# brick_lcd.net
KiCad netlist of a schematic drawn in EAGLE
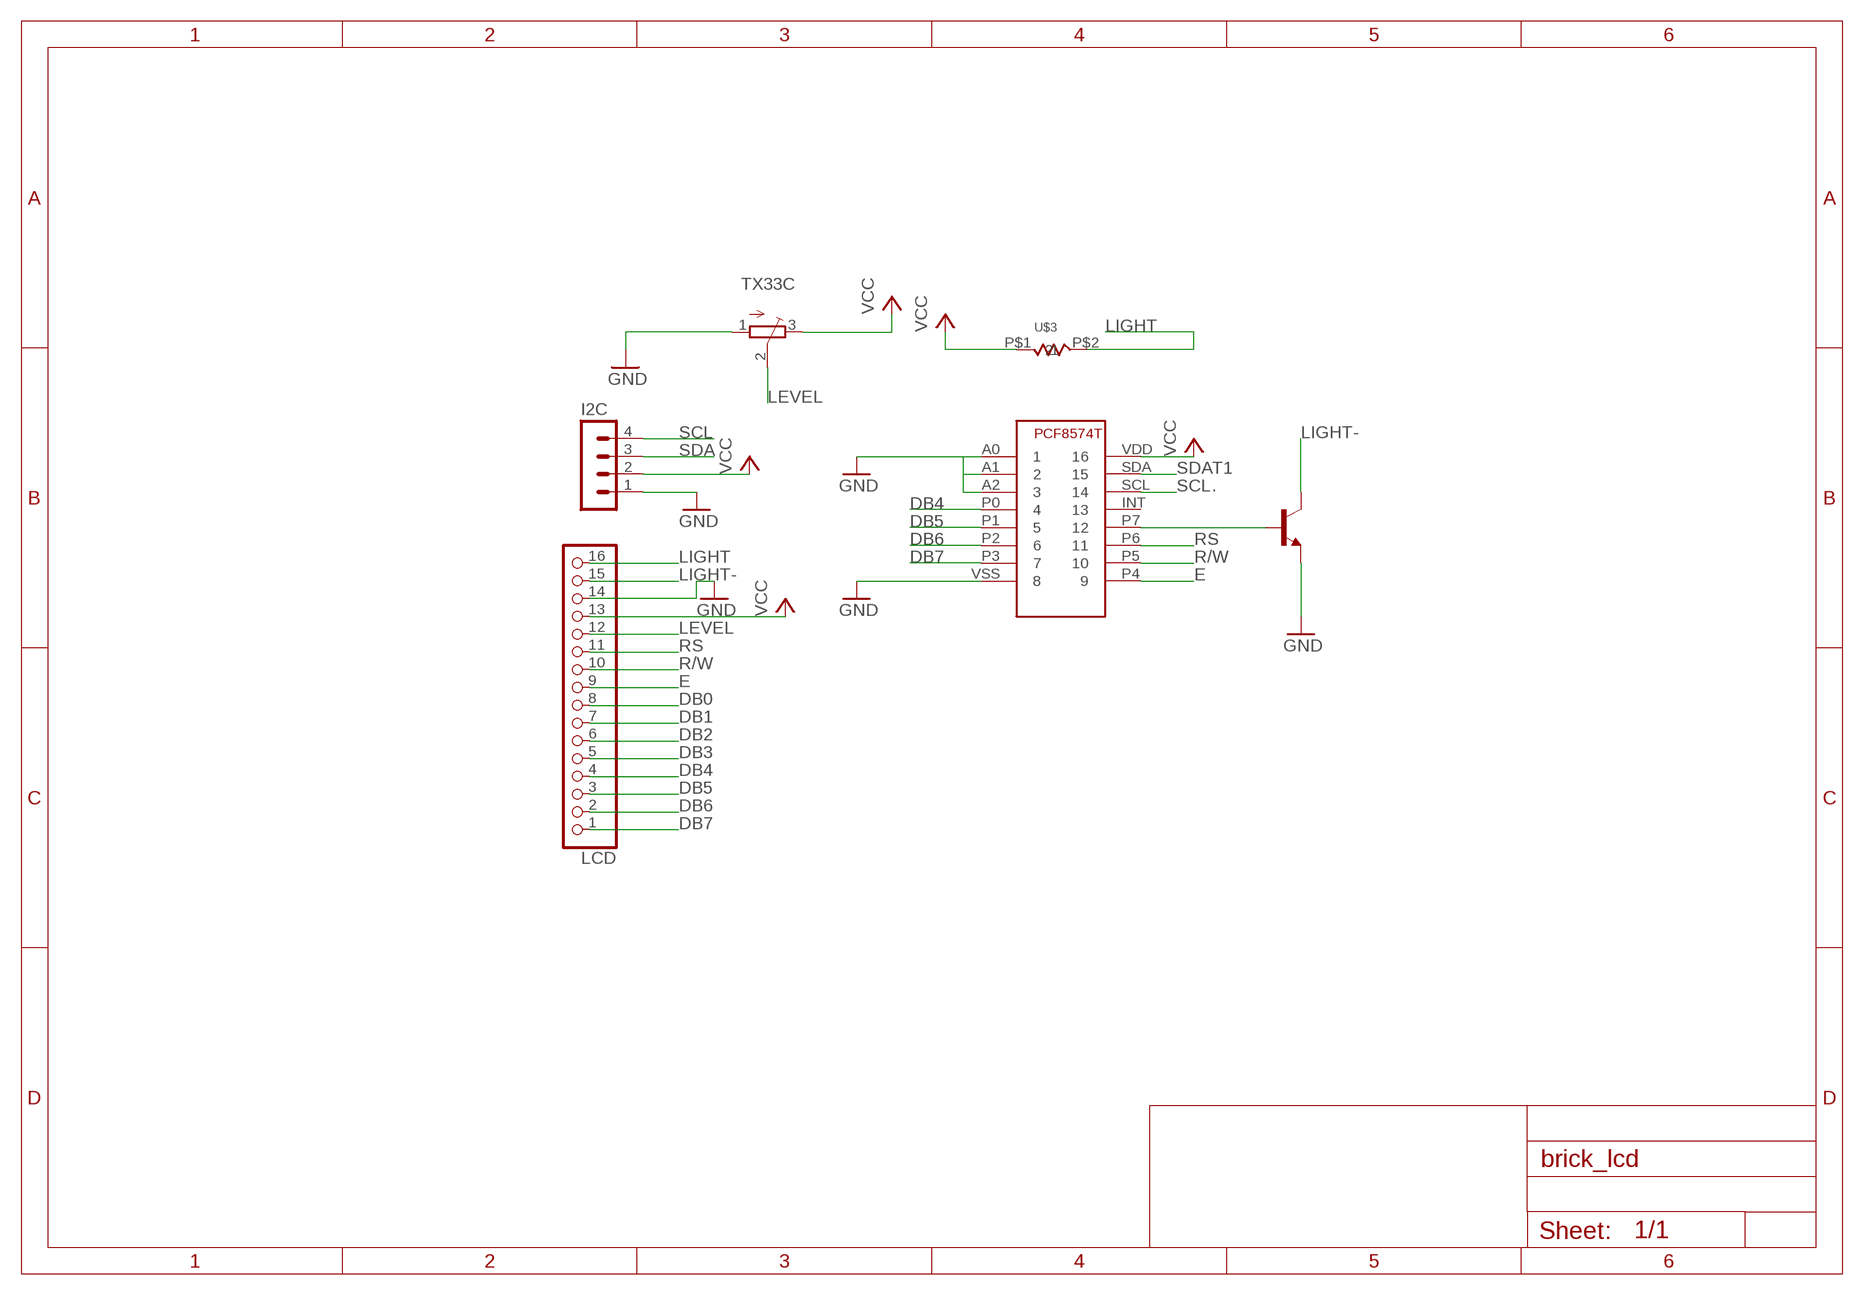
[diagram p0: schematic, sheet 1]

(export (version "E")
  (design (tool "Eeschema 10.0.6"))
  (components
    (comp (ref "I2C")
      (value "MA04-1")
      (footprint "eagle-import:MA04-1")
      (libsource (lib "eagle-import") (part "MA04-1"))
    )
    (comp (ref "LCD")
      (value "PINHD-1X16")
      (footprint "eagle-import:1X16")
      (libsource (lib "eagle-import") (part "PINHD-1X16"))
    )
    (comp (ref "T1")
      (value ".")
      (footprint "eagle-import:SOT23")
      (libsource (lib "eagle-import") (part "BC850"))
    )
    (comp (ref "TX33C")
      (value "TRIMPOTTC33X")
      (footprint "eagle-import:TC33X")
      (libsource (lib "eagle-import") (part "TRIMPOTTC33X"))
    )
    (comp (ref "U$1")
      (value "IC-PCF8574T")
      (footprint "eagle-import:SO16")
      (libsource (lib "eagle-import") (part "IC-PCF8574T"))
    )
    (comp (ref "U$3")
      (value "RESISTOR_0603")
      (footprint "eagle-import:RESISTOR_0603")
      (libsource (lib "eagle-import") (part "RESISTOR_0603"))
    )
  )
  (nets
    (net (code "1") (name "/DB0") (class "Default")
      (node (ref "LCD") (pin "8") (pinfunction "8_8") (pintype "passive"))
    )
    (net (code "2") (name "/DB1") (class "Default")
      (node (ref "LCD") (pin "7") (pinfunction "7_7") (pintype "passive"))
    )
    (net (code "3") (name "/DB2") (class "Default")
      (node (ref "LCD") (pin "6") (pinfunction "6_6") (pintype "passive"))
    )
    (net (code "4") (name "/DB3") (class "Default")
      (node (ref "LCD") (pin "5") (pinfunction "5_5") (pintype "passive"))
    )
    (net (code "5") (name "/DB4") (class "Default")
      (node (ref "LCD") (pin "4") (pinfunction "4_4") (pintype "passive"))
      (node (ref "U$1") (pin "P0") (pinfunction "4_P0") (pintype "bidirectional"))
    )
    (net (code "6") (name "/DB5") (class "Default")
      (node (ref "LCD") (pin "3") (pinfunction "3_3") (pintype "passive"))
      (node (ref "U$1") (pin "P1") (pinfunction "5_P1") (pintype "bidirectional"))
    )
    (net (code "7") (name "/DB6") (class "Default")
      (node (ref "LCD") (pin "2") (pinfunction "2_2") (pintype "passive"))
      (node (ref "U$1") (pin "P2") (pinfunction "6_P2") (pintype "bidirectional"))
    )
    (net (code "8") (name "/DB7") (class "Default")
      (node (ref "LCD") (pin "1") (pinfunction "1_1") (pintype "passive"))
      (node (ref "U$1") (pin "P3") (pinfunction "7_P3") (pintype "bidirectional"))
    )
    (net (code "9") (name "/E") (class "Default")
      (node (ref "LCD") (pin "9") (pinfunction "9_9") (pintype "passive"))
      (node (ref "U$1") (pin "P4") (pinfunction "9_P4") (pintype "bidirectional"))
    )
    (net (code "10") (name "/LEVEL") (class "Default")
      (node (ref "LCD") (pin "12") (pinfunction "12_12") (pintype "passive"))
      (node (ref "TX33C") (pin "2") (pinfunction "S_2") (pintype "passive"))
    )
    (net (code "11") (name "/LIGHT") (class "Default")
      (node (ref "LCD") (pin "16") (pinfunction "16_16") (pintype "passive"))
      (node (ref "U$3") (pin "P$2") (pinfunction "2_P$2") (pintype "bidirectional"))
    )
    (net (code "12") (name "/LIGHT-") (class "Default")
      (node (ref "LCD") (pin "15") (pinfunction "15_15") (pintype "passive"))
      (node (ref "T1") (pin "3") (pinfunction "C_3") (pintype "passive"))
    )
    (net (code "13") (name "/RS") (class "Default")
      (node (ref "LCD") (pin "11") (pinfunction "11_11") (pintype "passive"))
      (node (ref "U$1") (pin "P6") (pinfunction "11_P6") (pintype "bidirectional"))
    )
    (net (code "14") (name "/R{slash}W") (class "Default")
      (node (ref "LCD") (pin "10") (pinfunction "10_10") (pintype "passive"))
      (node (ref "U$1") (pin "P5") (pinfunction "10_P5") (pintype "bidirectional"))
    )
    (net (code "15") (name "/SCL") (class "Default")
      (node (ref "I2C") (pin "4") (pinfunction "4_4") (pintype "passive"))
      (node (ref "U$1") (pin "SCL") (pinfunction "14_SCL") (pintype "bidirectional"))
    )
    (net (code "16") (name "/SDA") (class "Default")
      (node (ref "I2C") (pin "3") (pinfunction "3_3") (pintype "passive"))
      (node (ref "U$1") (pin "SDA") (pinfunction "15_SDA") (pintype "bidirectional"))
    )
    (net (code "17") (name "GND") (class "Default")
      (node (ref "I2C") (pin "1") (pinfunction "1_1") (pintype "passive"))
      (node (ref "LCD") (pin "14") (pinfunction "14_14") (pintype "passive"))
      (node (ref "T1") (pin "2") (pinfunction "E_2") (pintype "passive"))
      (node (ref "TX33C") (pin "1") (pinfunction "A_1") (pintype "passive"))
      (node (ref "U$1") (pin "A0") (pinfunction "1_A0") (pintype "bidirectional"))
      (node (ref "U$1") (pin "A1") (pinfunction "2_A1") (pintype "bidirectional"))
      (node (ref "U$1") (pin "A2") (pinfunction "3_A2") (pintype "bidirectional"))
      (node (ref "U$1") (pin "VSS") (pinfunction "8_VSS") (pintype "bidirectional"))
    )
    (net (code "18") (name "Net-(T1-B)") (class "Default")
      (node (ref "T1") (pin "1") (pinfunction "B_1") (pintype "passive"))
      (node (ref "U$1") (pin "P7") (pinfunction "12_P7") (pintype "bidirectional"))
    )
    (net (code "19") (name "VCC") (class "Default")
      (node (ref "I2C") (pin "2") (pinfunction "2_2") (pintype "passive"))
      (node (ref "LCD") (pin "13") (pinfunction "13_13") (pintype "passive"))
      (node (ref "TX33C") (pin "3") (pinfunction "E_3") (pintype "passive"))
      (node (ref "U$1") (pin "VDD") (pinfunction "16_VDD") (pintype "bidirectional"))
      (node (ref "U$3") (pin "P$1") (pinfunction "1_P$1") (pintype "bidirectional"))
    )
    (net (code "20") (name "unconnected-(U$1-13-PadINT)") (class "Default")
      (node (ref "U$1") (pin "INT") (pinfunction "13_INT") (pintype "bidirectional"))
    )
  )
)
